# Multivibrator.net
KiCad netlist of a schematic drawn in Altium Designer
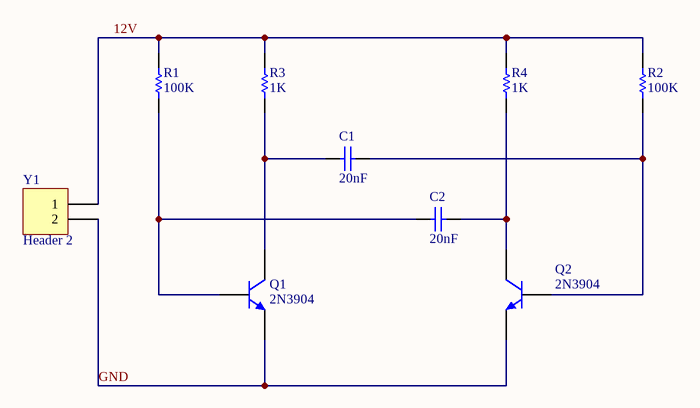
[diagram p0: Multivibrator.SchDoc]

(export (version "E")
  (design (tool "Eeschema 10.0.6"))
  (components
    (comp (ref "C1")
      (value "20nF")
      (footprint "RAD-0.3")
      (description "Capacitor")
      (fields (field (name "PUBLISHER") "Altium Limited"))
      (libsource (lib "Miscellaneous Devices") (part "Cap"))
    )
    (comp (ref "C2")
      (value "20nF")
      (footprint "RAD-0.3")
      (description "Capacitor")
      (fields (field (name "PUBLISHER") "Altium Limited"))
      (libsource (lib "Miscellaneous Devices") (part "Cap"))
    )
    (comp (ref "Q1")
      (value "2N3904")
      (footprint "TO-92A")
      (description "NPN General Purpose Amplifier")
      (fields (field (name "PUBLISHER") "Altium Limited"))
      (libsource (lib "Miscellaneous Devices") (part "2N3904"))
    )
    (comp (ref "Q2")
      (value "2N3904")
      (footprint "TO-92A")
      (description "NPN General Purpose Amplifier")
      (fields (field (name "PUBLISHER") "Altium Limited"))
      (libsource (lib "Miscellaneous Devices") (part "2N3904"))
    )
    (comp (ref "R1")
      (value "100K")
      (footprint "AXIAL-0.3")
      (description "Resistor")
      (fields (field (name "PUBLISHER") "Altium Limited"))
      (libsource (lib "Miscellaneous Devices") (part "Res1"))
    )
    (comp (ref "R2")
      (value "100K")
      (footprint "AXIAL-0.3")
      (description "Resistor")
      (fields (field (name "PUBLISHER") "Altium Limited"))
      (libsource (lib "Miscellaneous Devices") (part "Res1"))
    )
    (comp (ref "R3")
      (value "1K")
      (footprint "AXIAL-0.3")
      (description "Resistor")
      (fields (field (name "PUBLISHER") "Altium Limited"))
      (libsource (lib "Miscellaneous Devices") (part "Res1"))
    )
    (comp (ref "R4")
      (value "1K")
      (footprint "AXIAL-0.3")
      (description "Resistor")
      (fields (field (name "PUBLISHER") "Altium Limited"))
      (libsource (lib "Miscellaneous Devices") (part "Res1"))
    )
    (comp (ref "Y1")
      (value "Header 2")
      (footprint "HDR1X2")
      (description "Header, 2-Pin")
      (fields (field (name "PUBLISHER") "Altium Limited"))
      (libsource (lib "Miscellaneous Connectors") (part "Header 2"))
    )
  )
  (nets
    (net (code "1") (name "/12V") (class "Default")
      (node (ref "R1") (pin "2") (pinfunction "2_2") (pintype "passive"))
      (node (ref "R2") (pin "2") (pinfunction "2_2") (pintype "passive"))
      (node (ref "R3") (pin "2") (pinfunction "2_2") (pintype "passive"))
      (node (ref "R4") (pin "2") (pinfunction "2_2") (pintype "passive"))
      (node (ref "Y1") (pin "1") (pinfunction "1_1") (pintype "passive"))
    )
    (net (code "2") (name "/GND") (class "Default")
      (node (ref "Q1") (pin "1") (pinfunction "E_1") (pintype "passive"))
      (node (ref "Q2") (pin "1") (pinfunction "E_1") (pintype "passive"))
      (node (ref "Y1") (pin "2") (pinfunction "2_2") (pintype "passive"))
    )
    (net (code "3") (name "Net-(Q1-B)") (class "Default")
      (node (ref "C2") (pin "1") (pinfunction "1_1") (pintype "passive"))
      (node (ref "Q1") (pin "2") (pinfunction "B_2") (pintype "passive"))
      (node (ref "R1") (pin "1") (pinfunction "1_1") (pintype "passive"))
    )
    (net (code "4") (name "Net-(Q1-C)") (class "Default")
      (node (ref "C1") (pin "1") (pinfunction "1_1") (pintype "passive"))
      (node (ref "Q1") (pin "3") (pinfunction "C_3") (pintype "passive"))
      (node (ref "R3") (pin "1") (pinfunction "1_1") (pintype "passive"))
    )
    (net (code "5") (name "Net-(Q2-B)") (class "Default")
      (node (ref "C1") (pin "2") (pinfunction "2_2") (pintype "passive"))
      (node (ref "Q2") (pin "2") (pinfunction "B_2") (pintype "passive"))
      (node (ref "R2") (pin "1") (pinfunction "1_1") (pintype "passive"))
    )
    (net (code "6") (name "Net-(Q2-C)") (class "Default")
      (node (ref "C2") (pin "2") (pinfunction "2_2") (pintype "passive"))
      (node (ref "Q2") (pin "3") (pinfunction "C_3") (pintype "passive"))
      (node (ref "R4") (pin "1") (pinfunction "1_1") (pintype "passive"))
    )
  )
)
